# 2_pin_plank.net
KiCad netlist of a schematic drawn in EAGLE
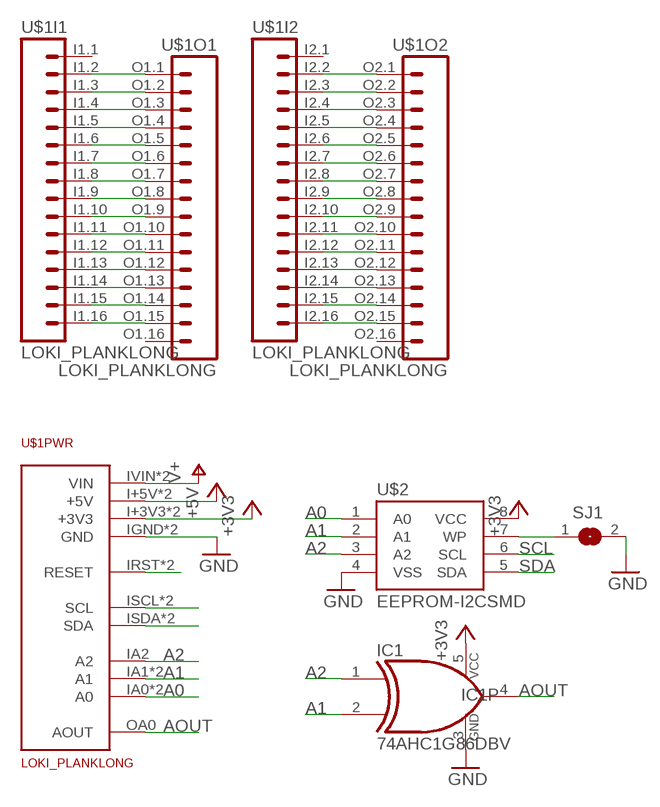
[diagram p0: schematic, sheet 1]

(export (version "E")
  (design (tool "Eeschema 10.0.6"))
  (components
    (comp (ref "IC1")
      (value "74AHC1G86DBV")
      (footprint "eagle-import:SOT23-5")
      (libsource (lib "eagle-import") (part "741G86DBVAHC"))
    )
    (comp (ref "SJ1") (value "SJ") (footprint "eagle-import:SJ") (libsource (lib "eagle-import") (part "SJ")))
    (comp (ref "U$1")
      (value "LOKI_PLANKLONG")
      (footprint "eagle-import:PLANK_LONG")
      (libsource (lib "eagle-import") (part "LOKI_PLANKLONG"))
    )
    (comp (ref "U$2")
      (value "EEPROM-I2CSMD")
      (footprint "eagle-import:SO08")
      (libsource (lib "eagle-import") (part "EEPROM-I2CSMD"))
    )
  )
  (nets
    (net (code "1") (name "+3V3") (class "Default")
      (node (ref "IC1") (pin "5") (pinfunction "VCC_5") (pintype "power_in"))
      (node (ref "U$1") (pin "I+3V3") (pinfunction "+3V3_I+3V3") (pintype "power_in"))
      (node (ref "U$1") (pin "O+3V3") (pinfunction "+3V3_O+3V3") (pintype "power_in"))
      (node (ref "U$2") (pin "8") (pinfunction "VCC_8") (pintype "power_in"))
    )
    (net (code "2") (name "+5V") (class "Default")
      (node (ref "U$1") (pin "I+5V") (pinfunction "+5V_I+5V") (pintype "power_in"))
      (node (ref "U$1") (pin "O+5V") (pinfunction "+5V_O+5V") (pintype "power_in"))
    )
    (net (code "3") (name "/A0") (class "Default")
      (node (ref "U$1") (pin "IA0") (pinfunction "A0_IA0") (pintype "output"))
      (node (ref "U$1") (pin "OA1") (pinfunction "A0_OA1") (pintype "output"))
      (node (ref "U$2") (pin "1") (pinfunction "A0_1") (pintype "bidirectional"))
    )
    (net (code "4") (name "/A1") (class "Default")
      (node (ref "IC1") (pin "2") (pinfunction "I1_2") (pintype "input"))
      (node (ref "U$1") (pin "IA1") (pinfunction "A1_IA1") (pintype "output"))
      (node (ref "U$1") (pin "OA2") (pinfunction "A1_OA2") (pintype "output"))
      (node (ref "U$2") (pin "2") (pinfunction "A1_2") (pintype "bidirectional"))
    )
    (net (code "5") (name "/A2") (class "Default")
      (node (ref "IC1") (pin "1") (pinfunction "I0_1") (pintype "input"))
      (node (ref "U$1") (pin "IA2") (pinfunction "A2_IA2") (pintype "output"))
      (node (ref "U$2") (pin "3") (pinfunction "A2_3") (pintype "bidirectional"))
    )
    (net (code "6") (name "/AOUT") (class "Default")
      (node (ref "IC1") (pin "4") (pinfunction "O_4") (pintype "output"))
      (node (ref "U$1") (pin "OA0") (pinfunction "AOUT_OA0") (pintype "input"))
    )
    (net (code "7") (name "/SCL") (class "Default")
      (node (ref "U$1") (pin "ISCL") (pinfunction "SCL_ISCL") (pintype "bidirectional"))
      (node (ref "U$1") (pin "OSCL") (pinfunction "SCL_OSCL") (pintype "bidirectional"))
      (node (ref "U$2") (pin "6") (pinfunction "SCL_6") (pintype "bidirectional"))
    )
    (net (code "8") (name "/SDA") (class "Default")
      (node (ref "U$1") (pin "ISDA") (pinfunction "SDA_ISDA") (pintype "bidirectional"))
      (node (ref "U$1") (pin "OSDA") (pinfunction "SDA_OSDA") (pintype "bidirectional"))
      (node (ref "U$2") (pin "5") (pinfunction "SDA_5") (pintype "bidirectional"))
    )
    (net (code "9") (name "GND") (class "Default")
      (node (ref "IC1") (pin "3") (pinfunction "GND_3") (pintype "power_in"))
      (node (ref "SJ1") (pin "2") (pinfunction "2_2") (pintype "passive"))
      (node (ref "U$1") (pin "IGND") (pinfunction "GND_IGND") (pintype "power_in"))
      (node (ref "U$1") (pin "OGND") (pinfunction "GND_OGND") (pintype "power_in"))
      (node (ref "U$2") (pin "4") (pinfunction "VSS_4") (pintype "power_in"))
    )
    (net (code "10") (name "Net-(U$1A-2)") (class "Default")
      (node (ref "U$1") (pin "I1.2") (pinfunction "2_I1.2") (pintype "passive"))
      (node (ref "U$1") (pin "O1.1") (pinfunction "1_O1.1") (pintype "passive"))
    )
    (net (code "11") (name "Net-(U$1A-3)") (class "Default")
      (node (ref "U$1") (pin "I1.3") (pinfunction "3_I1.3") (pintype "passive"))
      (node (ref "U$1") (pin "O1.2") (pinfunction "2_O1.2") (pintype "passive"))
    )
    (net (code "12") (name "Net-(U$1A-4)") (class "Default")
      (node (ref "U$1") (pin "I1.4") (pinfunction "4_I1.4") (pintype "passive"))
      (node (ref "U$1") (pin "O1.3") (pinfunction "3_O1.3") (pintype "passive"))
    )
    (net (code "13") (name "Net-(U$1A-5)") (class "Default")
      (node (ref "U$1") (pin "I1.5") (pinfunction "5_I1.5") (pintype "passive"))
      (node (ref "U$1") (pin "O1.4") (pinfunction "4_O1.4") (pintype "passive"))
    )
    (net (code "14") (name "Net-(U$1A-6)") (class "Default")
      (node (ref "U$1") (pin "I1.6") (pinfunction "6_I1.6") (pintype "passive"))
      (node (ref "U$1") (pin "O1.5") (pinfunction "5_O1.5") (pintype "passive"))
    )
    (net (code "15") (name "Net-(U$1A-7)") (class "Default")
      (node (ref "U$1") (pin "I1.7") (pinfunction "7_I1.7") (pintype "passive"))
      (node (ref "U$1") (pin "O1.6") (pinfunction "6_O1.6") (pintype "passive"))
    )
    (net (code "16") (name "Net-(U$1A-8)") (class "Default")
      (node (ref "U$1") (pin "I1.8") (pinfunction "8_I1.8") (pintype "passive"))
      (node (ref "U$1") (pin "O1.7") (pinfunction "7_O1.7") (pintype "passive"))
    )
    (net (code "17") (name "Net-(U$1A-9)") (class "Default")
      (node (ref "U$1") (pin "I1.9") (pinfunction "9_I1.9") (pintype "passive"))
      (node (ref "U$1") (pin "O1.8") (pinfunction "8_O1.8") (pintype "passive"))
    )
    (net (code "18") (name "Net-(U$1A-10)") (class "Default")
      (node (ref "U$1") (pin "I1.10") (pinfunction "10_I1.10") (pintype "passive"))
      (node (ref "U$1") (pin "O1.9") (pinfunction "9_O1.9") (pintype "passive"))
    )
    (net (code "19") (name "Net-(U$1A-11)") (class "Default")
      (node (ref "U$1") (pin "I1.11") (pinfunction "11_I1.11") (pintype "passive"))
      (node (ref "U$1") (pin "O1.10") (pinfunction "10_O1.10") (pintype "passive"))
    )
    (net (code "20") (name "Net-(U$1A-12)") (class "Default")
      (node (ref "U$1") (pin "I1.12") (pinfunction "12_I1.12") (pintype "passive"))
      (node (ref "U$1") (pin "O1.11") (pinfunction "11_O1.11") (pintype "passive"))
    )
    (net (code "21") (name "Net-(U$1A-13)") (class "Default")
      (node (ref "U$1") (pin "I1.13") (pinfunction "13_I1.13") (pintype "passive"))
      (node (ref "U$1") (pin "O1.12") (pinfunction "12_O1.12") (pintype "passive"))
    )
    (net (code "22") (name "Net-(U$1A-14)") (class "Default")
      (node (ref "U$1") (pin "I1.14") (pinfunction "14_I1.14") (pintype "passive"))
      (node (ref "U$1") (pin "O1.13") (pinfunction "13_O1.13") (pintype "passive"))
    )
    (net (code "23") (name "Net-(U$1A-15)") (class "Default")
      (node (ref "U$1") (pin "I1.15") (pinfunction "15_I1.15") (pintype "passive"))
      (node (ref "U$1") (pin "O1.14") (pinfunction "14_O1.14") (pintype "passive"))
    )
    (net (code "24") (name "Net-(U$1A-16)") (class "Default")
      (node (ref "U$1") (pin "I1.16") (pinfunction "16_I1.16") (pintype "passive"))
      (node (ref "U$1") (pin "O1.15") (pinfunction "15_O1.15") (pintype "passive"))
    )
    (net (code "25") (name "Net-(U$1B-2)") (class "Default")
      (node (ref "U$1") (pin "I2.2") (pinfunction "2_I2.2") (pintype "passive"))
      (node (ref "U$1") (pin "O2.1") (pinfunction "1_O2.1") (pintype "passive"))
    )
    (net (code "26") (name "Net-(U$1B-3)") (class "Default")
      (node (ref "U$1") (pin "I2.3") (pinfunction "3_I2.3") (pintype "passive"))
      (node (ref "U$1") (pin "O2.2") (pinfunction "2_O2.2") (pintype "passive"))
    )
    (net (code "27") (name "Net-(U$1B-4)") (class "Default")
      (node (ref "U$1") (pin "I2.4") (pinfunction "4_I2.4") (pintype "passive"))
      (node (ref "U$1") (pin "O2.3") (pinfunction "3_O2.3") (pintype "passive"))
    )
    (net (code "28") (name "Net-(U$1B-5)") (class "Default")
      (node (ref "U$1") (pin "I2.5") (pinfunction "5_I2.5") (pintype "passive"))
      (node (ref "U$1") (pin "O2.4") (pinfunction "4_O2.4") (pintype "passive"))
    )
    (net (code "29") (name "Net-(U$1B-6)") (class "Default")
      (node (ref "U$1") (pin "I2.6") (pinfunction "6_I2.6") (pintype "passive"))
      (node (ref "U$1") (pin "O2.5") (pinfunction "5_O2.5") (pintype "passive"))
    )
    (net (code "30") (name "Net-(U$1B-7)") (class "Default")
      (node (ref "U$1") (pin "I2.7") (pinfunction "7_I2.7") (pintype "passive"))
      (node (ref "U$1") (pin "O2.6") (pinfunction "6_O2.6") (pintype "passive"))
    )
    (net (code "31") (name "Net-(U$1B-8)") (class "Default")
      (node (ref "U$1") (pin "I2.8") (pinfunction "8_I2.8") (pintype "passive"))
      (node (ref "U$1") (pin "O2.7") (pinfunction "7_O2.7") (pintype "passive"))
    )
    (net (code "32") (name "Net-(U$1B-9)") (class "Default")
      (node (ref "U$1") (pin "I2.9") (pinfunction "9_I2.9") (pintype "passive"))
      (node (ref "U$1") (pin "O2.8") (pinfunction "8_O2.8") (pintype "passive"))
    )
    (net (code "33") (name "Net-(U$1B-10)") (class "Default")
      (node (ref "U$1") (pin "I2.10") (pinfunction "10_I2.10") (pintype "passive"))
      (node (ref "U$1") (pin "O2.9") (pinfunction "9_O2.9") (pintype "passive"))
    )
    (net (code "34") (name "Net-(U$1B-11)") (class "Default")
      (node (ref "U$1") (pin "I2.11") (pinfunction "11_I2.11") (pintype "passive"))
      (node (ref "U$1") (pin "O2.10") (pinfunction "10_O2.10") (pintype "passive"))
    )
    (net (code "35") (name "Net-(U$1B-12)") (class "Default")
      (node (ref "U$1") (pin "I2.12") (pinfunction "12_I2.12") (pintype "passive"))
      (node (ref "U$1") (pin "O2.11") (pinfunction "11_O2.11") (pintype "passive"))
    )
    (net (code "36") (name "Net-(U$1B-13)") (class "Default")
      (node (ref "U$1") (pin "I2.13") (pinfunction "13_I2.13") (pintype "passive"))
      (node (ref "U$1") (pin "O2.12") (pinfunction "12_O2.12") (pintype "passive"))
    )
    (net (code "37") (name "Net-(U$1B-14)") (class "Default")
      (node (ref "U$1") (pin "I2.14") (pinfunction "14_I2.14") (pintype "passive"))
      (node (ref "U$1") (pin "O2.13") (pinfunction "13_O2.13") (pintype "passive"))
    )
    (net (code "38") (name "Net-(U$1B-15)") (class "Default")
      (node (ref "U$1") (pin "I2.15") (pinfunction "15_I2.15") (pintype "passive"))
      (node (ref "U$1") (pin "O2.14") (pinfunction "14_O2.14") (pintype "passive"))
    )
    (net (code "39") (name "Net-(U$1B-16)") (class "Default")
      (node (ref "U$1") (pin "I2.16") (pinfunction "16_I2.16") (pintype "passive"))
      (node (ref "U$1") (pin "O2.15") (pinfunction "15_O2.15") (pintype "passive"))
    )
    (net (code "40") (name "Net-(U$1E-RESET-PadIRST)") (class "Default")
      (node (ref "U$1") (pin "IRST") (pinfunction "RESET_IRST") (pintype "input"))
      (node (ref "U$1") (pin "ORST") (pinfunction "RESET_ORST") (pintype "input"))
    )
    (net (code "41") (name "Net-(U$2-WP)") (class "Default")
      (node (ref "SJ1") (pin "1") (pinfunction "1_1") (pintype "passive"))
      (node (ref "U$2") (pin "7") (pinfunction "WP_7") (pintype "bidirectional"))
    )
    (net (code "42") (name "V+") (class "Default")
      (node (ref "U$1") (pin "IVIN") (pinfunction "VIN_IVIN") (pintype "power_in"))
      (node (ref "U$1") (pin "OVIN") (pinfunction "VIN_OVIN") (pintype "power_in"))
    )
    (net (code "43") (name "unconnected-(U$1A-1-PadI1.1)") (class "Default")
      (node (ref "U$1") (pin "I1.1") (pinfunction "1_I1.1") (pintype "passive"))
    )
    (net (code "44") (name "unconnected-(U$1B-1-PadI2.1)") (class "Default")
      (node (ref "U$1") (pin "I2.1") (pinfunction "1_I2.1") (pintype "passive"))
    )
    (net (code "45") (name "unconnected-(U$1C-16-PadO1.16)") (class "Default")
      (node (ref "U$1") (pin "O1.16") (pinfunction "16_O1.16") (pintype "passive"))
    )
    (net (code "46") (name "unconnected-(U$1D-16-PadO2.16)") (class "Default")
      (node (ref "U$1") (pin "O2.16") (pinfunction "16_O2.16") (pintype "passive"))
    )
  )
)
